# Worst_case.net
KiCad netlist of a schematic drawn in Altium Designer
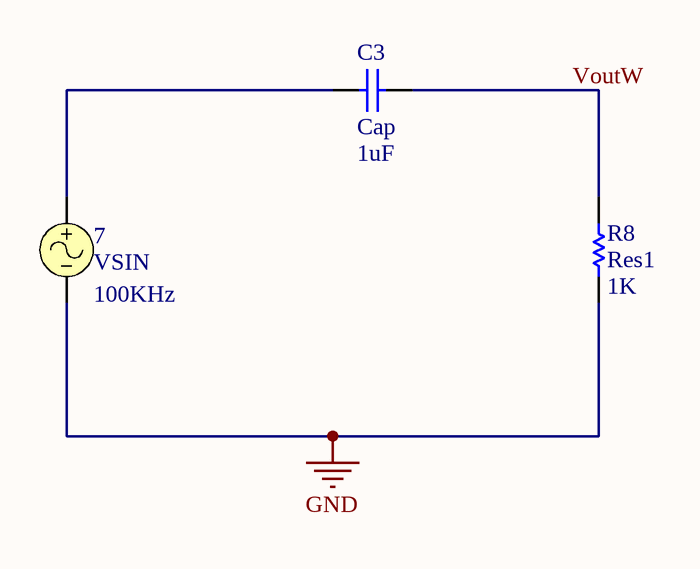
[diagram p0: Worst case.SchDoc]

(export (version "E")
  (design (tool "Eeschema 10.0.6"))
  (components
    (comp (ref "7")
      (value "VSIN")
      (description "Sinusoidal Voltage Source")
      (fields (field (name "FREQUENCY") "100KHz") (field (name "PUBLISHER") "Altium Limited"))
      (libsource (lib "Simulation Sources") (part "VSIN"))
    )
    (comp (ref "C3")
      (value "Cap")
      (footprint "RAD-0.3")
      (description "Capacitor")
      (fields (field (name "ALTIUM_VALUE") "1uF") (field (name "PUBLISHER") "Altium Limited"))
      (libsource (lib "Miscellaneous Devices") (part "Cap"))
    )
    (comp (ref "R8")
      (value "Res1")
      (footprint "AXIAL-0.3")
      (description "Resistor")
      (fields (field (name "ALTIUM_VALUE") "1K") (field (name "PUBLISHER") "Altium Limited"))
      (libsource (lib "Miscellaneous Devices") (part "Res1"))
    )
  )
  (nets
    (net (code "1") (name "/VoutW") (class "Default")
      (node (ref "C3") (pin "2") (pinfunction "2_2") (pintype "passive"))
      (node (ref "R8") (pin "2") (pinfunction "2_2") (pintype "passive"))
    )
    (net (code "2") (name "GND") (class "Default")
      (node (ref "7") (pin "2") (pinfunction "2_2") (pintype "passive"))
      (node (ref "R8") (pin "1") (pinfunction "1_1") (pintype "passive"))
    )
    (net (code "3") (name "Net-(7-Pad1)") (class "Default")
      (node (ref "7") (pin "1") (pinfunction "1_1") (pintype "passive"))
      (node (ref "C3") (pin "1") (pinfunction "1_1") (pintype "passive"))
    )
  )
)
